# AmbaSat-06-SI1132-A10-GMR.net
KiCad netlist of a schematic drawn in EAGLE
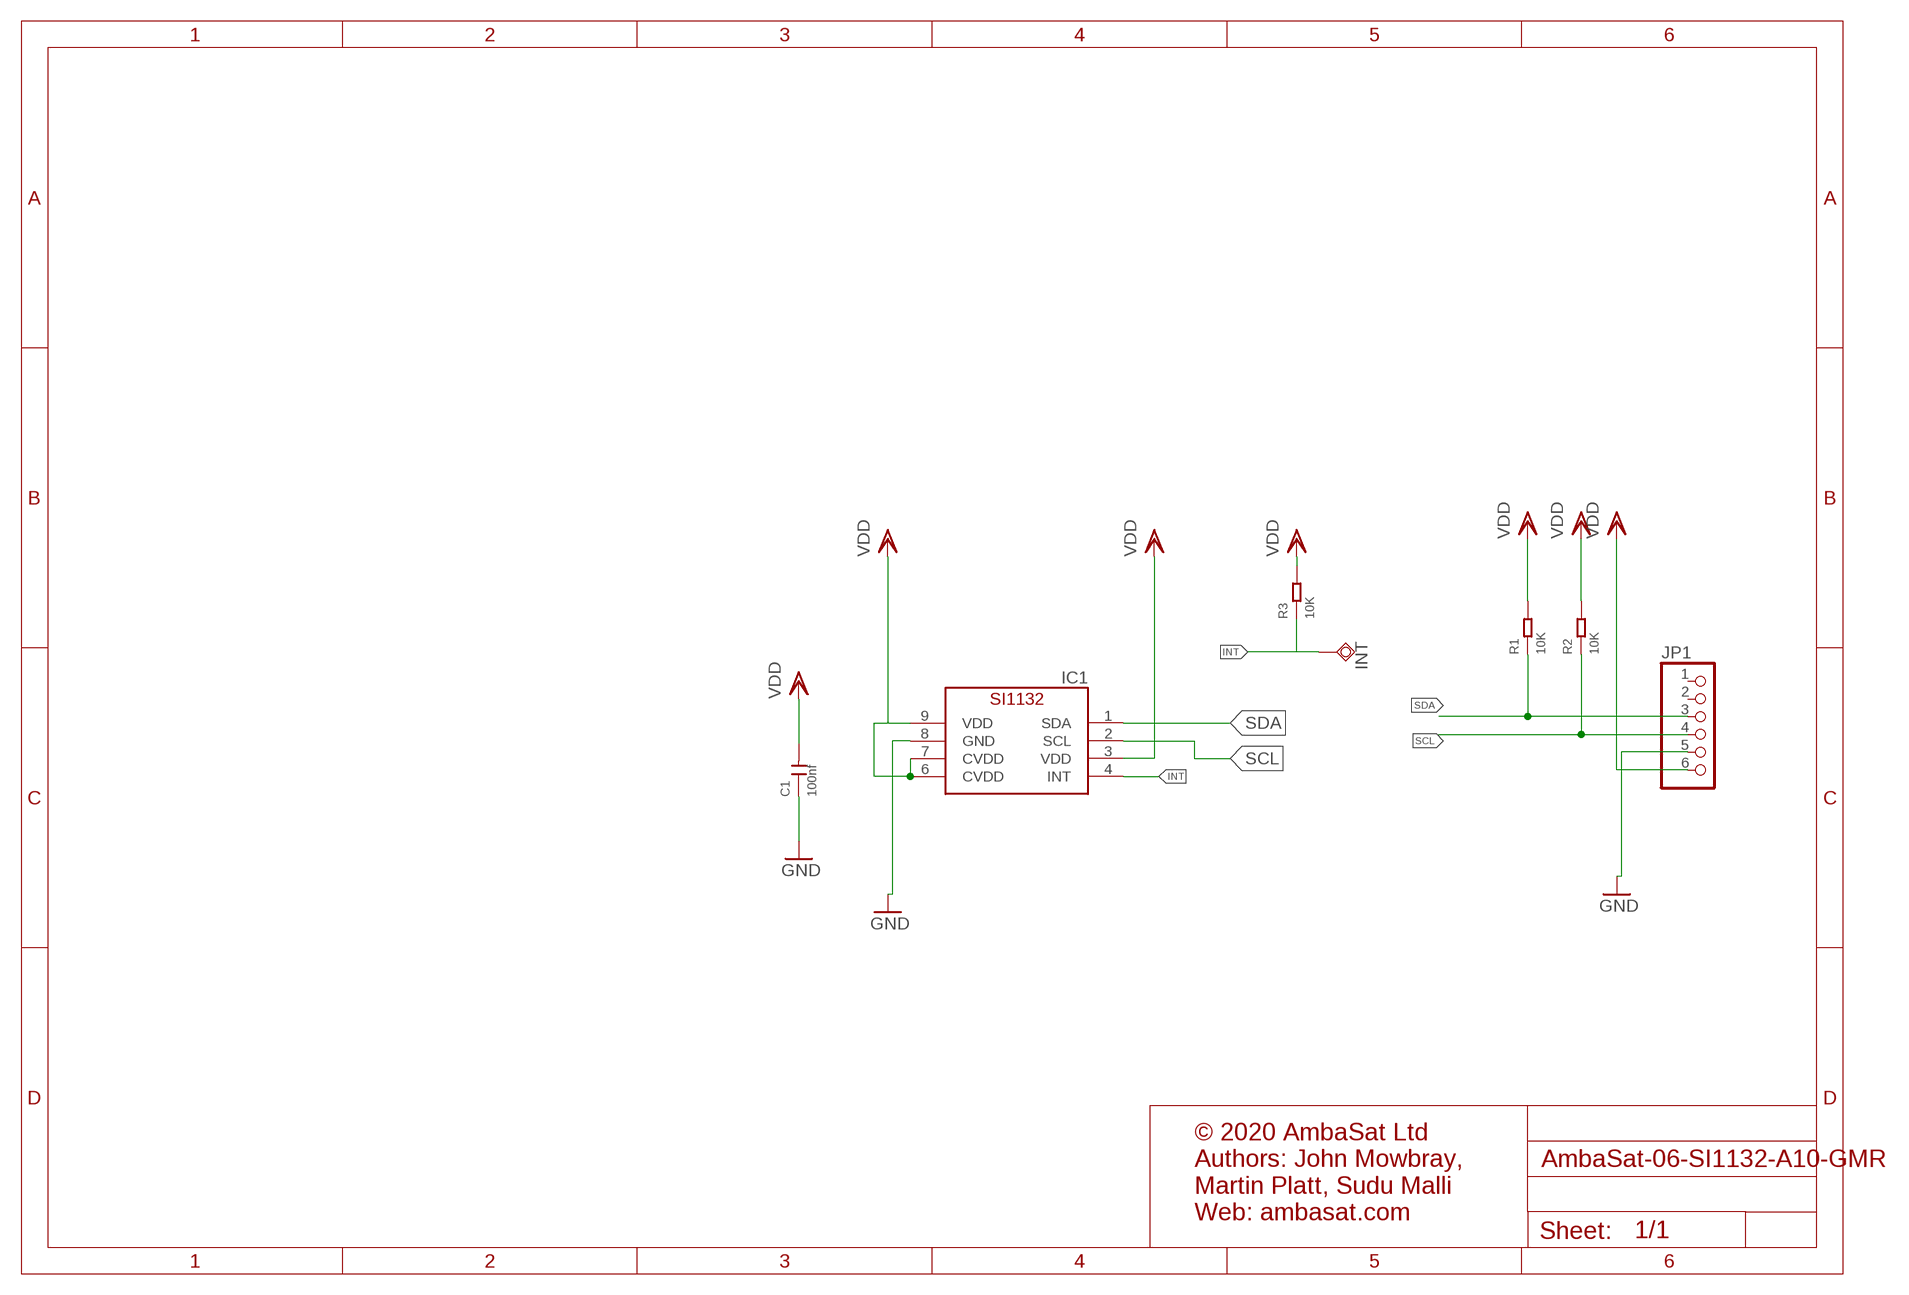
[diagram p0: schematic, sheet 1]

(export (version "E")
  (design (tool "Eeschema 10.0.6"))
  (components
    (comp (ref "C1")
      (value "100nf")
      (footprint "eagle-import:C0805")
      (fields (field (name "MPN") "CC0805KRX7R9BB104"))
      (libsource (lib "eagle-import") (part "CERAMIC-100NF-50V-10%-X7R(0805)"))
    )
    (comp (ref "IC1")
      (value "SL-SI1132")
      (footprint "eagle-import:SILICONLABS-SI1132")
      (libsource (lib "eagle-import") (part "SL-SI1132"))
    )
    (comp (ref "INT")
      (value "TESTPAD_TPSQTP12R")
      (footprint "eagle-import:TESTPAD_TP12R")
      (libsource (lib "eagle-import") (part "TESTPAD_TPSQTP12R"))
    )
    (comp (ref "JP1")
      (value "HEADER-1X6")
      (footprint "eagle-import:1X06_OVAL")
      (libsource (lib "eagle-import") (part "HEADER-1X6"))
    )
    (comp (ref "R1")
      (value "10K")
      (footprint "eagle-import:R0805")
      (fields (field (name "MPN") "RC0805FR-0710KL"))
      (libsource (lib "eagle-import") (part "SMD-RES-10K-1%-1/8W(0805)"))
    )
    (comp (ref "R2")
      (value "10K")
      (footprint "eagle-import:R0805")
      (fields (field (name "MPN") "RC0805FR-0710KL"))
      (libsource (lib "eagle-import") (part "SMD-RES-10K-1%-1/8W(0805)"))
    )
    (comp (ref "R3")
      (value "10K")
      (footprint "eagle-import:R0805")
      (fields (field (name "MPN") "RC0805FR-0710KL"))
      (libsource (lib "eagle-import") (part "SMD-RES-10K-1%-1/8W(0805)"))
    )
  )
  (nets
    (net (code "1") (name "GND") (class "Default")
      (node (ref "C1") (pin "1") (pinfunction "1_1") (pintype "passive"))
      (node (ref "IC1") (pin "8") (pinfunction "GND_8") (pintype "bidirectional"))
      (node (ref "JP1") (pin "5") (pinfunction "5_5") (pintype "passive"))
    )
    (net (code "2") (name "INT") (class "Default")
      (node (ref "IC1") (pin "4") (pinfunction "INT_4") (pintype "bidirectional"))
      (node (ref "INT") (pin "TP") (pinfunction "TP_TP") (pintype "input"))
      (node (ref "R3") (pin "1") (pinfunction "1_1") (pintype "passive"))
    )
    (net (code "3") (name "SCL") (class "Default")
      (node (ref "IC1") (pin "2") (pinfunction "SCL_2") (pintype "bidirectional"))
      (node (ref "JP1") (pin "4") (pinfunction "4_4") (pintype "passive"))
      (node (ref "R2") (pin "1") (pinfunction "1_1") (pintype "passive"))
    )
    (net (code "4") (name "SDA") (class "Default")
      (node (ref "IC1") (pin "1") (pinfunction "SDA_1") (pintype "bidirectional"))
      (node (ref "JP1") (pin "3") (pinfunction "3_3") (pintype "passive"))
      (node (ref "R1") (pin "1") (pinfunction "1_1") (pintype "passive"))
    )
    (net (code "5") (name "VDD") (class "Default")
      (node (ref "C1") (pin "2") (pinfunction "2_2") (pintype "passive"))
      (node (ref "IC1") (pin "3") (pinfunction "VDD_3") (pintype "bidirectional"))
      (node (ref "IC1") (pin "6") (pinfunction "CVDD_6") (pintype "bidirectional"))
      (node (ref "IC1") (pin "7") (pinfunction "CVDD_7") (pintype "bidirectional"))
      (node (ref "IC1") (pin "9") (pinfunction "VDD_9") (pintype "bidirectional"))
      (node (ref "JP1") (pin "6") (pinfunction "6_6") (pintype "passive"))
      (node (ref "R1") (pin "2") (pinfunction "2_2") (pintype "passive"))
      (node (ref "R2") (pin "2") (pinfunction "2_2") (pintype "passive"))
      (node (ref "R3") (pin "2") (pinfunction "2_2") (pintype "passive"))
    )
    (net (code "6") (name "unconnected-(JP1-Pad1)") (class "Default")
      (node (ref "JP1") (pin "1") (pinfunction "1_1") (pintype "passive"))
    )
    (net (code "7") (name "unconnected-(JP1-Pad2)") (class "Default")
      (node (ref "JP1") (pin "2") (pinfunction "2_2") (pintype "passive"))
    )
  )
)
